# Main_Board.net
KiCad netlist of a schematic drawn in EAGLE
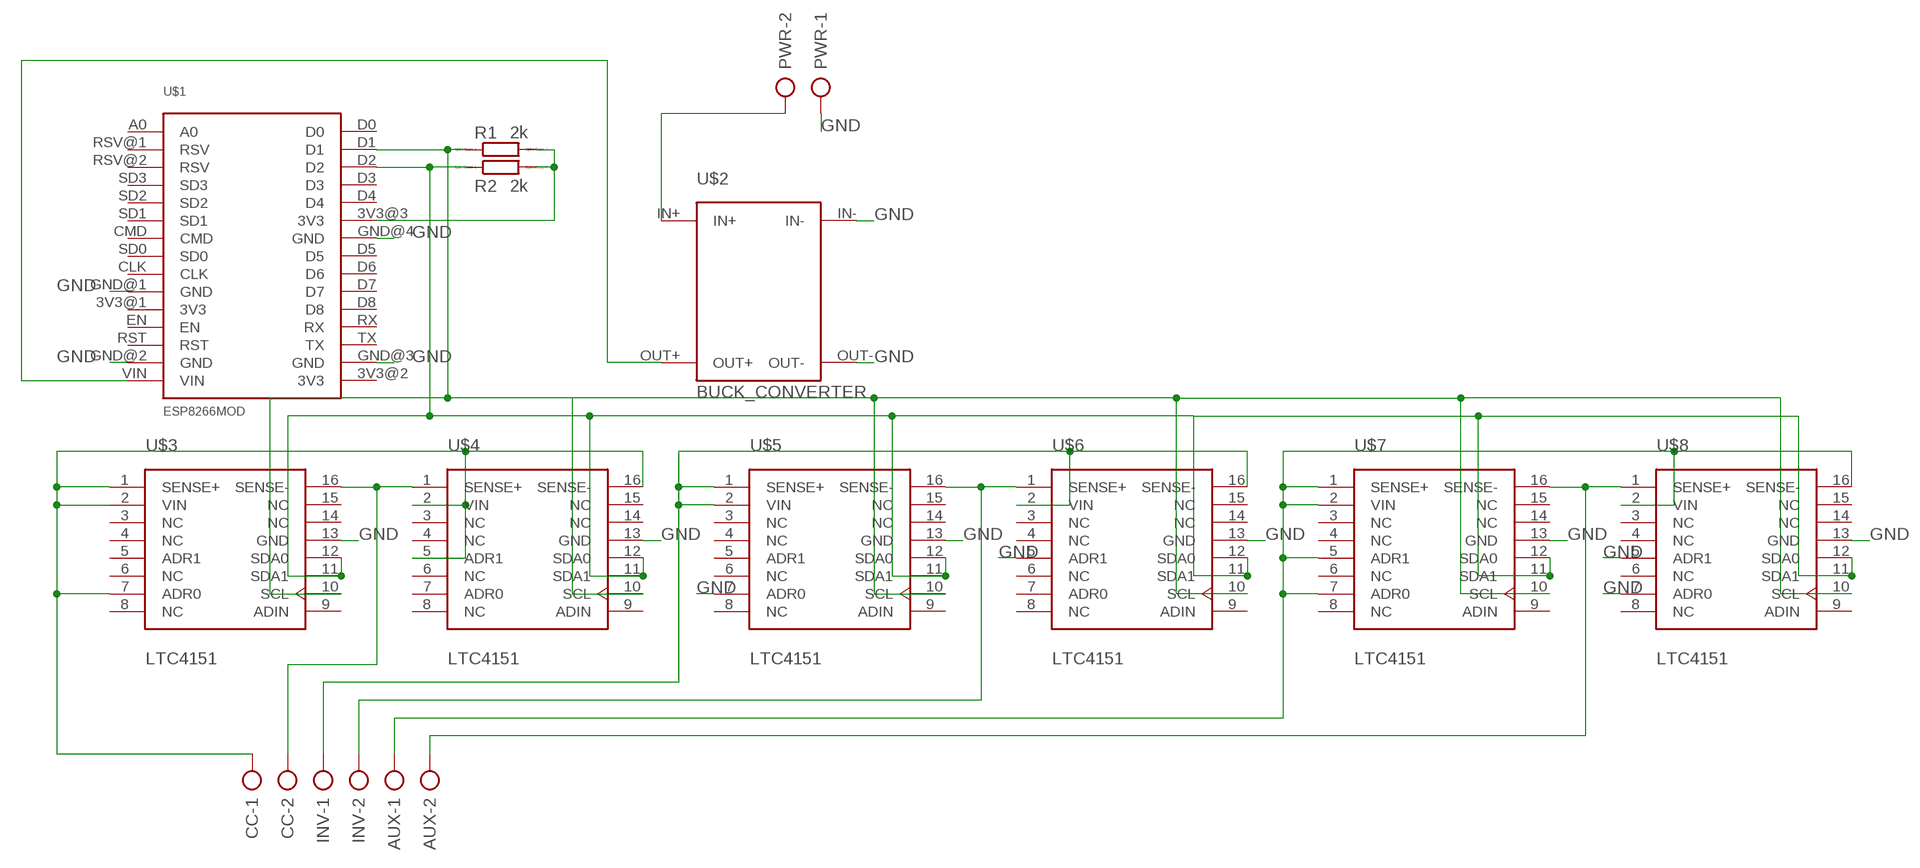
[diagram p0: schematic, sheet 1]

(export (version "E")
  (design (tool "Eeschema 10.0.6"))
  (components
    (comp (ref "AUX")
      (value "AK500/2")
      (footprint "eagle-import:AK500_2")
      (libsource (lib "eagle-import") (part "AK500/2"))
    )
    (comp (ref "CC")
      (value "AK500/2")
      (footprint "eagle-import:AK500_2")
      (libsource (lib "eagle-import") (part "AK500/2"))
    )
    (comp (ref "INV")
      (value "AK500/2")
      (footprint "eagle-import:AK500_2")
      (libsource (lib "eagle-import") (part "AK500/2"))
    )
    (comp (ref "PWR")
      (value "AK500/2")
      (footprint "eagle-import:AK500_2")
      (libsource (lib "eagle-import") (part "AK500/2"))
    )
    (comp (ref "R1")
      (value "2k")
      (footprint "eagle-import:0207_10")
      (libsource (lib "eagle-import") (part "R0207/10"))
    )
    (comp (ref "R2")
      (value "2k")
      (footprint "eagle-import:0207_10")
      (libsource (lib "eagle-import") (part "R0207/10"))
    )
    (comp (ref "U$1")
      (value "ESP8266MOD")
      (footprint "eagle-import:ESP8266MOD")
      (libsource (lib "eagle-import") (part "ESP8266MOD"))
    )
    (comp (ref "U$2")
      (value "BUCK_CONVERTER")
      (footprint "eagle-import:BUCK_CONVERTER")
      (libsource (lib "eagle-import") (part "BUCK_CONVERTER"))
    )
    (comp (ref "U$3")
      (value "LTC4151")
      (footprint "eagle-import:SO16")
      (libsource (lib "eagle-import") (part "LTC4151"))
    )
    (comp (ref "U$4")
      (value "LTC4151")
      (footprint "eagle-import:SO16")
      (libsource (lib "eagle-import") (part "LTC4151"))
    )
    (comp (ref "U$5")
      (value "LTC4151")
      (footprint "eagle-import:SO16")
      (libsource (lib "eagle-import") (part "LTC4151"))
    )
    (comp (ref "U$6")
      (value "LTC4151")
      (footprint "eagle-import:SO16")
      (libsource (lib "eagle-import") (part "LTC4151"))
    )
    (comp (ref "U$7")
      (value "LTC4151")
      (footprint "eagle-import:SO16")
      (libsource (lib "eagle-import") (part "LTC4151"))
    )
    (comp (ref "U$8")
      (value "LTC4151")
      (footprint "eagle-import:SO16")
      (libsource (lib "eagle-import") (part "LTC4151"))
    )
  )
  (nets
    (net (code "1") (name "/GND") (class "Default")
      (node (ref "PWR") (pin "1") (pinfunction "KL_1") (pintype "passive"))
      (node (ref "U$1") (pin "GND@1") (pinfunction "GND_GND@1") (pintype "bidirectional"))
      (node (ref "U$1") (pin "GND@2") (pinfunction "GND_GND@2") (pintype "bidirectional"))
      (node (ref "U$1") (pin "GND@3") (pinfunction "GND_GND@3") (pintype "bidirectional"))
      (node (ref "U$1") (pin "GND@4") (pinfunction "GND_GND@4") (pintype "bidirectional"))
      (node (ref "U$2") (pin "IN-") (pinfunction "IN-_IN-") (pintype "bidirectional"))
      (node (ref "U$2") (pin "OUT-") (pinfunction "OUT-_OUT-") (pintype "bidirectional"))
      (node (ref "U$3") (pin "13") (pinfunction "GND_13") (pintype "power_in"))
      (node (ref "U$4") (pin "13") (pinfunction "GND_13") (pintype "power_in"))
      (node (ref "U$5") (pin "13") (pinfunction "GND_13") (pintype "power_in"))
      (node (ref "U$5") (pin "7") (pinfunction "ADR0_7") (pintype "input"))
      (node (ref "U$6") (pin "13") (pinfunction "GND_13") (pintype "power_in"))
      (node (ref "U$6") (pin "5") (pinfunction "ADR1_5") (pintype "input"))
      (node (ref "U$7") (pin "13") (pinfunction "GND_13") (pintype "power_in"))
      (node (ref "U$8") (pin "13") (pinfunction "GND_13") (pintype "power_in"))
      (node (ref "U$8") (pin "5") (pinfunction "ADR1_5") (pintype "input"))
      (node (ref "U$8") (pin "7") (pinfunction "ADR0_7") (pintype "input"))
    )
    (net (code "2") (name "Net-(AUXA-KL)") (class "Default")
      (node (ref "AUX") (pin "1") (pinfunction "KL_1") (pintype "passive"))
      (node (ref "U$7") (pin "1") (pinfunction "SENSE+_1") (pintype "input"))
      (node (ref "U$7") (pin "2") (pinfunction "VIN_2") (pintype "power_in"))
      (node (ref "U$7") (pin "5") (pinfunction "ADR1_5") (pintype "input"))
      (node (ref "U$7") (pin "7") (pinfunction "ADR0_7") (pintype "input"))
      (node (ref "U$8") (pin "16") (pinfunction "SENSE-_16") (pintype "input"))
      (node (ref "U$8") (pin "2") (pinfunction "VIN_2") (pintype "power_in"))
    )
    (net (code "3") (name "Net-(AUXB-KL)") (class "Default")
      (node (ref "AUX") (pin "2") (pinfunction "KL_2") (pintype "passive"))
      (node (ref "U$7") (pin "16") (pinfunction "SENSE-_16") (pintype "input"))
      (node (ref "U$8") (pin "1") (pinfunction "SENSE+_1") (pintype "input"))
    )
    (net (code "4") (name "Net-(CCA-KL)") (class "Default")
      (node (ref "CC") (pin "1") (pinfunction "KL_1") (pintype "passive"))
      (node (ref "U$3") (pin "1") (pinfunction "SENSE+_1") (pintype "input"))
      (node (ref "U$3") (pin "2") (pinfunction "VIN_2") (pintype "power_in"))
      (node (ref "U$3") (pin "7") (pinfunction "ADR0_7") (pintype "input"))
      (node (ref "U$4") (pin "16") (pinfunction "SENSE-_16") (pintype "input"))
      (node (ref "U$4") (pin "2") (pinfunction "VIN_2") (pintype "power_in"))
      (node (ref "U$4") (pin "5") (pinfunction "ADR1_5") (pintype "input"))
    )
    (net (code "5") (name "Net-(CCB-KL)") (class "Default")
      (node (ref "CC") (pin "2") (pinfunction "KL_2") (pintype "passive"))
      (node (ref "U$3") (pin "16") (pinfunction "SENSE-_16") (pintype "input"))
      (node (ref "U$4") (pin "1") (pinfunction "SENSE+_1") (pintype "input"))
    )
    (net (code "6") (name "Net-(INVA-KL)") (class "Default")
      (node (ref "INV") (pin "1") (pinfunction "KL_1") (pintype "passive"))
      (node (ref "U$5") (pin "1") (pinfunction "SENSE+_1") (pintype "input"))
      (node (ref "U$5") (pin "2") (pinfunction "VIN_2") (pintype "power_in"))
      (node (ref "U$6") (pin "16") (pinfunction "SENSE-_16") (pintype "input"))
      (node (ref "U$6") (pin "2") (pinfunction "VIN_2") (pintype "power_in"))
    )
    (net (code "7") (name "Net-(INVB-KL)") (class "Default")
      (node (ref "INV") (pin "2") (pinfunction "KL_2") (pintype "passive"))
      (node (ref "U$5") (pin "16") (pinfunction "SENSE-_16") (pintype "input"))
      (node (ref "U$6") (pin "1") (pinfunction "SENSE+_1") (pintype "input"))
    )
    (net (code "8") (name "Net-(PWRB-KL)") (class "Default")
      (node (ref "PWR") (pin "2") (pinfunction "KL_2") (pintype "passive"))
      (node (ref "U$2") (pin "IN+") (pinfunction "IN+_IN+") (pintype "bidirectional"))
    )
    (net (code "9") (name "Net-(R1-Pad2)") (class "Default")
      (node (ref "R1") (pin "2") (pinfunction "2_2") (pintype "passive"))
      (node (ref "R2") (pin "2") (pinfunction "2_2") (pintype "passive"))
      (node (ref "U$1") (pin "3V3@3") (pinfunction "3V3_3V3@3") (pintype "bidirectional"))
    )
    (net (code "10") (name "Net-(U$1-PadVIN)") (class "Default")
      (node (ref "U$1") (pin "VIN") (pinfunction "VIN_VIN") (pintype "bidirectional"))
      (node (ref "U$2") (pin "OUT+") (pinfunction "OUT+_OUT+") (pintype "bidirectional"))
    )
    (net (code "11") (name "Net-(U$3-SCL)") (class "Default")
      (node (ref "R1") (pin "1") (pinfunction "1_1") (pintype "passive"))
      (node (ref "U$1") (pin "D1") (pinfunction "D1_D1") (pintype "bidirectional"))
      (node (ref "U$3") (pin "10") (pinfunction "SCL_10") (pintype "bidirectional"))
      (node (ref "U$4") (pin "10") (pinfunction "SCL_10") (pintype "bidirectional"))
      (node (ref "U$5") (pin "10") (pinfunction "SCL_10") (pintype "bidirectional"))
      (node (ref "U$6") (pin "10") (pinfunction "SCL_10") (pintype "bidirectional"))
      (node (ref "U$7") (pin "10") (pinfunction "SCL_10") (pintype "bidirectional"))
      (node (ref "U$8") (pin "10") (pinfunction "SCL_10") (pintype "bidirectional"))
    )
    (net (code "12") (name "Net-(U$3-SDA0)") (class "Default")
      (node (ref "R2") (pin "1") (pinfunction "1_1") (pintype "passive"))
      (node (ref "U$1") (pin "D2") (pinfunction "D2_D2") (pintype "bidirectional"))
      (node (ref "U$3") (pin "11") (pinfunction "SDA1_11") (pintype "input"))
      (node (ref "U$3") (pin "12") (pinfunction "SDA0_12") (pintype "output"))
      (node (ref "U$4") (pin "11") (pinfunction "SDA1_11") (pintype "input"))
      (node (ref "U$4") (pin "12") (pinfunction "SDA0_12") (pintype "output"))
      (node (ref "U$5") (pin "11") (pinfunction "SDA1_11") (pintype "input"))
      (node (ref "U$5") (pin "12") (pinfunction "SDA0_12") (pintype "output"))
      (node (ref "U$6") (pin "11") (pinfunction "SDA1_11") (pintype "input"))
      (node (ref "U$6") (pin "12") (pinfunction "SDA0_12") (pintype "output"))
      (node (ref "U$7") (pin "11") (pinfunction "SDA1_11") (pintype "input"))
      (node (ref "U$7") (pin "12") (pinfunction "SDA0_12") (pintype "output"))
      (node (ref "U$8") (pin "11") (pinfunction "SDA1_11") (pintype "input"))
      (node (ref "U$8") (pin "12") (pinfunction "SDA0_12") (pintype "output"))
    )
    (net (code "13") (name "unconnected-(U$1-3V3-Pad3V3@1)") (class "Default")
      (node (ref "U$1") (pin "3V3@1") (pinfunction "3V3_3V3@1") (pintype "bidirectional"))
    )
    (net (code "14") (name "unconnected-(U$1-3V3-Pad3V3@2)") (class "Default")
      (node (ref "U$1") (pin "3V3@2") (pinfunction "3V3_3V3@2") (pintype "bidirectional"))
    )
    (net (code "15") (name "unconnected-(U$1-PadA0)") (class "Default")
      (node (ref "U$1") (pin "A0") (pinfunction "A0_A0") (pintype "bidirectional"))
    )
    (net (code "16") (name "unconnected-(U$1-PadCLK)") (class "Default")
      (node (ref "U$1") (pin "CLK") (pinfunction "CLK_CLK") (pintype "bidirectional"))
    )
    (net (code "17") (name "unconnected-(U$1-PadCMD)") (class "Default")
      (node (ref "U$1") (pin "CMD") (pinfunction "CMD_CMD") (pintype "bidirectional"))
    )
    (net (code "18") (name "unconnected-(U$1-PadD0)") (class "Default")
      (node (ref "U$1") (pin "D0") (pinfunction "D0_D0") (pintype "bidirectional"))
    )
    (net (code "19") (name "unconnected-(U$1-PadD3)") (class "Default")
      (node (ref "U$1") (pin "D3") (pinfunction "D3_D3") (pintype "bidirectional"))
    )
    (net (code "20") (name "unconnected-(U$1-PadD4)") (class "Default")
      (node (ref "U$1") (pin "D4") (pinfunction "D4_D4") (pintype "bidirectional"))
    )
    (net (code "21") (name "unconnected-(U$1-PadD5)") (class "Default")
      (node (ref "U$1") (pin "D5") (pinfunction "D5_D5") (pintype "bidirectional"))
    )
    (net (code "22") (name "unconnected-(U$1-PadD6)") (class "Default")
      (node (ref "U$1") (pin "D6") (pinfunction "D6_D6") (pintype "bidirectional"))
    )
    (net (code "23") (name "unconnected-(U$1-PadD7)") (class "Default")
      (node (ref "U$1") (pin "D7") (pinfunction "D7_D7") (pintype "bidirectional"))
    )
    (net (code "24") (name "unconnected-(U$1-PadD8)") (class "Default")
      (node (ref "U$1") (pin "D8") (pinfunction "D8_D8") (pintype "bidirectional"))
    )
    (net (code "25") (name "unconnected-(U$1-PadEN)") (class "Default")
      (node (ref "U$1") (pin "EN") (pinfunction "EN_EN") (pintype "bidirectional"))
    )
    (net (code "26") (name "unconnected-(U$1-PadRST)") (class "Default")
      (node (ref "U$1") (pin "RST") (pinfunction "RST_RST") (pintype "bidirectional"))
    )
    (net (code "27") (name "unconnected-(U$1-PadRX)") (class "Default")
      (node (ref "U$1") (pin "RX") (pinfunction "RX_RX") (pintype "bidirectional"))
    )
    (net (code "28") (name "unconnected-(U$1-PadSD0)") (class "Default")
      (node (ref "U$1") (pin "SD0") (pinfunction "SD0_SD0") (pintype "bidirectional"))
    )
    (net (code "29") (name "unconnected-(U$1-PadSD1)") (class "Default")
      (node (ref "U$1") (pin "SD1") (pinfunction "SD1_SD1") (pintype "bidirectional"))
    )
    (net (code "30") (name "unconnected-(U$1-PadSD2)") (class "Default")
      (node (ref "U$1") (pin "SD2") (pinfunction "SD2_SD2") (pintype "bidirectional"))
    )
    (net (code "31") (name "unconnected-(U$1-PadSD3)") (class "Default")
      (node (ref "U$1") (pin "SD3") (pinfunction "SD3_SD3") (pintype "bidirectional"))
    )
    (net (code "32") (name "unconnected-(U$1-PadTX)") (class "Default")
      (node (ref "U$1") (pin "TX") (pinfunction "TX_TX") (pintype "bidirectional"))
    )
    (net (code "33") (name "unconnected-(U$1-RSV-PadRSV@1)") (class "Default")
      (node (ref "U$1") (pin "RSV@1") (pinfunction "RSV_RSV@1") (pintype "bidirectional"))
    )
    (net (code "34") (name "unconnected-(U$1-RSV-PadRSV@2)") (class "Default")
      (node (ref "U$1") (pin "RSV@2") (pinfunction "RSV_RSV@2") (pintype "bidirectional"))
    )
    (net (code "35") (name "unconnected-(U$3-ADIN-Pad9)") (class "Default")
      (node (ref "U$3") (pin "9") (pinfunction "ADIN_9") (pintype "input"))
    )
    (net (code "36") (name "unconnected-(U$3-ADR1-Pad5)") (class "Default")
      (node (ref "U$3") (pin "5") (pinfunction "ADR1_5") (pintype "input"))
    )
    (net (code "37") (name "unconnected-(U$3-NC-Pad3)") (class "Default")
      (node (ref "U$3") (pin "3") (pinfunction "NC_3") (pintype "no_connect"))
    )
    (net (code "38") (name "unconnected-(U$3-NC-Pad4)") (class "Default")
      (node (ref "U$3") (pin "4") (pinfunction "NC_4") (pintype "no_connect"))
    )
    (net (code "39") (name "unconnected-(U$3-NC-Pad6)") (class "Default")
      (node (ref "U$3") (pin "6") (pinfunction "NC_6") (pintype "no_connect"))
    )
    (net (code "40") (name "unconnected-(U$3-NC-Pad8)") (class "Default")
      (node (ref "U$3") (pin "8") (pinfunction "NC_8") (pintype "no_connect"))
    )
    (net (code "41") (name "unconnected-(U$3-NC-Pad14)") (class "Default")
      (node (ref "U$3") (pin "14") (pinfunction "NC_14") (pintype "no_connect"))
    )
    (net (code "42") (name "unconnected-(U$3-NC-Pad15)") (class "Default")
      (node (ref "U$3") (pin "15") (pinfunction "NC_15") (pintype "no_connect"))
    )
    (net (code "43") (name "unconnected-(U$4-ADIN-Pad9)") (class "Default")
      (node (ref "U$4") (pin "9") (pinfunction "ADIN_9") (pintype "input"))
    )
    (net (code "44") (name "unconnected-(U$4-ADR0-Pad7)") (class "Default")
      (node (ref "U$4") (pin "7") (pinfunction "ADR0_7") (pintype "input"))
    )
    (net (code "45") (name "unconnected-(U$4-NC-Pad3)") (class "Default")
      (node (ref "U$4") (pin "3") (pinfunction "NC_3") (pintype "no_connect"))
    )
    (net (code "46") (name "unconnected-(U$4-NC-Pad4)") (class "Default")
      (node (ref "U$4") (pin "4") (pinfunction "NC_4") (pintype "no_connect"))
    )
    (net (code "47") (name "unconnected-(U$4-NC-Pad6)") (class "Default")
      (node (ref "U$4") (pin "6") (pinfunction "NC_6") (pintype "no_connect"))
    )
    (net (code "48") (name "unconnected-(U$4-NC-Pad8)") (class "Default")
      (node (ref "U$4") (pin "8") (pinfunction "NC_8") (pintype "no_connect"))
    )
    (net (code "49") (name "unconnected-(U$4-NC-Pad14)") (class "Default")
      (node (ref "U$4") (pin "14") (pinfunction "NC_14") (pintype "no_connect"))
    )
    (net (code "50") (name "unconnected-(U$4-NC-Pad15)") (class "Default")
      (node (ref "U$4") (pin "15") (pinfunction "NC_15") (pintype "no_connect"))
    )
    (net (code "51") (name "unconnected-(U$5-ADIN-Pad9)") (class "Default")
      (node (ref "U$5") (pin "9") (pinfunction "ADIN_9") (pintype "input"))
    )
    (net (code "52") (name "unconnected-(U$5-ADR1-Pad5)") (class "Default")
      (node (ref "U$5") (pin "5") (pinfunction "ADR1_5") (pintype "input"))
    )
    (net (code "53") (name "unconnected-(U$5-NC-Pad3)") (class "Default")
      (node (ref "U$5") (pin "3") (pinfunction "NC_3") (pintype "no_connect"))
    )
    (net (code "54") (name "unconnected-(U$5-NC-Pad4)") (class "Default")
      (node (ref "U$5") (pin "4") (pinfunction "NC_4") (pintype "no_connect"))
    )
    (net (code "55") (name "unconnected-(U$5-NC-Pad6)") (class "Default")
      (node (ref "U$5") (pin "6") (pinfunction "NC_6") (pintype "no_connect"))
    )
    (net (code "56") (name "unconnected-(U$5-NC-Pad8)") (class "Default")
      (node (ref "U$5") (pin "8") (pinfunction "NC_8") (pintype "no_connect"))
    )
    (net (code "57") (name "unconnected-(U$5-NC-Pad14)") (class "Default")
      (node (ref "U$5") (pin "14") (pinfunction "NC_14") (pintype "no_connect"))
    )
    (net (code "58") (name "unconnected-(U$5-NC-Pad15)") (class "Default")
      (node (ref "U$5") (pin "15") (pinfunction "NC_15") (pintype "no_connect"))
    )
    (net (code "59") (name "unconnected-(U$6-ADIN-Pad9)") (class "Default")
      (node (ref "U$6") (pin "9") (pinfunction "ADIN_9") (pintype "input"))
    )
    (net (code "60") (name "unconnected-(U$6-ADR0-Pad7)") (class "Default")
      (node (ref "U$6") (pin "7") (pinfunction "ADR0_7") (pintype "input"))
    )
    (net (code "61") (name "unconnected-(U$6-NC-Pad3)") (class "Default")
      (node (ref "U$6") (pin "3") (pinfunction "NC_3") (pintype "no_connect"))
    )
    (net (code "62") (name "unconnected-(U$6-NC-Pad4)") (class "Default")
      (node (ref "U$6") (pin "4") (pinfunction "NC_4") (pintype "no_connect"))
    )
    (net (code "63") (name "unconnected-(U$6-NC-Pad6)") (class "Default")
      (node (ref "U$6") (pin "6") (pinfunction "NC_6") (pintype "no_connect"))
    )
    (net (code "64") (name "unconnected-(U$6-NC-Pad8)") (class "Default")
      (node (ref "U$6") (pin "8") (pinfunction "NC_8") (pintype "no_connect"))
    )
    (net (code "65") (name "unconnected-(U$6-NC-Pad14)") (class "Default")
      (node (ref "U$6") (pin "14") (pinfunction "NC_14") (pintype "no_connect"))
    )
    (net (code "66") (name "unconnected-(U$6-NC-Pad15)") (class "Default")
      (node (ref "U$6") (pin "15") (pinfunction "NC_15") (pintype "no_connect"))
    )
    (net (code "67") (name "unconnected-(U$7-ADIN-Pad9)") (class "Default")
      (node (ref "U$7") (pin "9") (pinfunction "ADIN_9") (pintype "input"))
    )
    (net (code "68") (name "unconnected-(U$7-NC-Pad3)") (class "Default")
      (node (ref "U$7") (pin "3") (pinfunction "NC_3") (pintype "no_connect"))
    )
    (net (code "69") (name "unconnected-(U$7-NC-Pad4)") (class "Default")
      (node (ref "U$7") (pin "4") (pinfunction "NC_4") (pintype "no_connect"))
    )
    (net (code "70") (name "unconnected-(U$7-NC-Pad6)") (class "Default")
      (node (ref "U$7") (pin "6") (pinfunction "NC_6") (pintype "no_connect"))
    )
    (net (code "71") (name "unconnected-(U$7-NC-Pad8)") (class "Default")
      (node (ref "U$7") (pin "8") (pinfunction "NC_8") (pintype "no_connect"))
    )
    (net (code "72") (name "unconnected-(U$7-NC-Pad14)") (class "Default")
      (node (ref "U$7") (pin "14") (pinfunction "NC_14") (pintype "no_connect"))
    )
    (net (code "73") (name "unconnected-(U$7-NC-Pad15)") (class "Default")
      (node (ref "U$7") (pin "15") (pinfunction "NC_15") (pintype "no_connect"))
    )
    (net (code "74") (name "unconnected-(U$8-ADIN-Pad9)") (class "Default")
      (node (ref "U$8") (pin "9") (pinfunction "ADIN_9") (pintype "input"))
    )
    (net (code "75") (name "unconnected-(U$8-NC-Pad3)") (class "Default")
      (node (ref "U$8") (pin "3") (pinfunction "NC_3") (pintype "no_connect"))
    )
    (net (code "76") (name "unconnected-(U$8-NC-Pad4)") (class "Default")
      (node (ref "U$8") (pin "4") (pinfunction "NC_4") (pintype "no_connect"))
    )
    (net (code "77") (name "unconnected-(U$8-NC-Pad6)") (class "Default")
      (node (ref "U$8") (pin "6") (pinfunction "NC_6") (pintype "no_connect"))
    )
    (net (code "78") (name "unconnected-(U$8-NC-Pad8)") (class "Default")
      (node (ref "U$8") (pin "8") (pinfunction "NC_8") (pintype "no_connect"))
    )
    (net (code "79") (name "unconnected-(U$8-NC-Pad14)") (class "Default")
      (node (ref "U$8") (pin "14") (pinfunction "NC_14") (pintype "no_connect"))
    )
    (net (code "80") (name "unconnected-(U$8-NC-Pad15)") (class "Default")
      (node (ref "U$8") (pin "15") (pinfunction "NC_15") (pintype "no_connect"))
    )
  )
)
